# esp01-prog.net
KiCad netlist of a schematic drawn in EAGLE
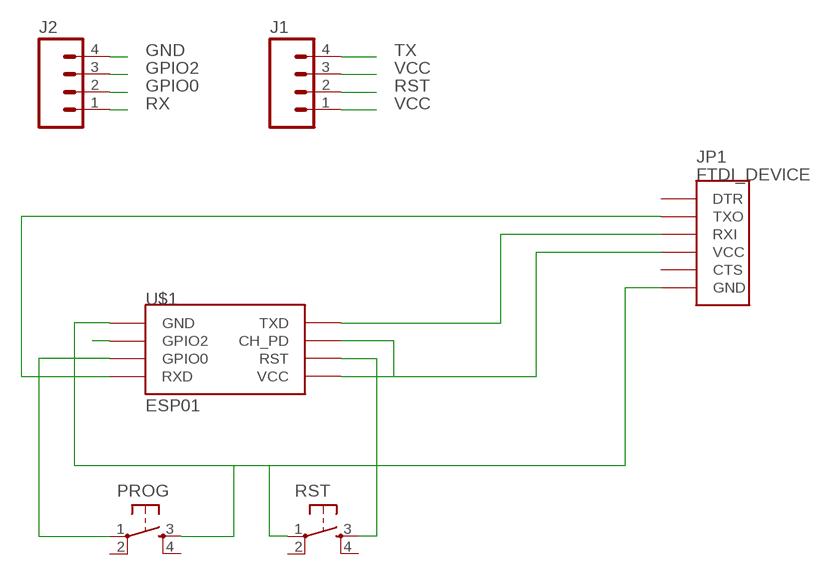
[diagram p0: schematic, sheet 1]

(export (version "E")
  (design (tool "Eeschema 10.0.6"))
  (components
    (comp (ref "J1")
      (value "M04PTH")
      (footprint "eagle-import:1X04")
      (libsource (lib "eagle-import") (part "M04PTH"))
    )
    (comp (ref "J2")
      (value "M04PTH")
      (footprint "eagle-import:1X04")
      (libsource (lib "eagle-import") (part "M04PTH"))
    )
    (comp (ref "JP1")
      (value "FTDI_DEVICE")
      (footprint "eagle-import:FTDI_DEVICE_SIDE")
      (libsource (lib "eagle-import") (part "FTDI_DEVICE"))
    )
    (comp (ref "PROG")
      (value "TACTILE-SWITCH-PTH")
      (footprint "eagle-import:TAC-SWITCH-PTH")
      (libsource (lib "eagle-import") (part "TACTILE-SWITCH-PTH"))
    )
    (comp (ref "RST")
      (value "TACTILE-SWITCH-PTH")
      (footprint "eagle-import:TAC-SWITCH-PTH")
      (libsource (lib "eagle-import") (part "TACTILE-SWITCH-PTH"))
    )
    (comp (ref "U$1")
      (value "ESP01")
      (footprint "eagle-import:ESP01")
      (libsource (lib "eagle-import") (part "ESP01"))
    )
  )
  (nets
    (net (code "1") (name "/GND") (class "Default")
      (node (ref "J2") (pin "4") (pinfunction "4_4") (pintype "passive"))
      (node (ref "JP1") (pin "P$6") (pinfunction "GND_P$6") (pintype "bidirectional"))
      (node (ref "PROG") (pin "3") (pinfunction "3_3") (pintype "passive"))
      (node (ref "RST") (pin "1") (pinfunction "1_1") (pintype "passive"))
      (node (ref "U$1") (pin "GND") (pinfunction "GND_GND") (pintype "bidirectional"))
    )
    (net (code "2") (name "/GPIO0") (class "Default")
      (node (ref "J2") (pin "2") (pinfunction "2_2") (pintype "passive"))
      (node (ref "PROG") (pin "1") (pinfunction "1_1") (pintype "passive"))
      (node (ref "U$1") (pin "GPIO0") (pinfunction "GPIO0_GPIO0") (pintype "bidirectional"))
    )
    (net (code "3") (name "/GPIO2") (class "Default")
      (node (ref "J2") (pin "3") (pinfunction "3_3") (pintype "passive"))
      (node (ref "U$1") (pin "GPIO2") (pinfunction "GPIO2_GPIO2") (pintype "bidirectional"))
    )
    (net (code "4") (name "/RST") (class "Default")
      (node (ref "J1") (pin "2") (pinfunction "2_2") (pintype "passive"))
      (node (ref "RST") (pin "3") (pinfunction "3_3") (pintype "passive"))
      (node (ref "U$1") (pin "RST") (pinfunction "RST_RST") (pintype "bidirectional"))
    )
    (net (code "5") (name "/RX") (class "Default")
      (node (ref "J2") (pin "1") (pinfunction "1_1") (pintype "passive"))
      (node (ref "JP1") (pin "P$2") (pinfunction "TXO_P$2") (pintype "bidirectional"))
      (node (ref "U$1") (pin "RX") (pinfunction "RXD_RX") (pintype "bidirectional"))
    )
    (net (code "6") (name "/TX") (class "Default")
      (node (ref "J1") (pin "4") (pinfunction "4_4") (pintype "passive"))
      (node (ref "JP1") (pin "P$3") (pinfunction "RXI_P$3") (pintype "bidirectional"))
      (node (ref "U$1") (pin "TX") (pinfunction "TXD_TX") (pintype "bidirectional"))
    )
    (net (code "7") (name "/VCC") (class "Default")
      (node (ref "J1") (pin "1") (pinfunction "1_1") (pintype "passive"))
      (node (ref "J1") (pin "3") (pinfunction "3_3") (pintype "passive"))
      (node (ref "JP1") (pin "P$4") (pinfunction "VCC_P$4") (pintype "bidirectional"))
      (node (ref "U$1") (pin "CH_PD") (pinfunction "CH_PD_CH_PD") (pintype "bidirectional"))
      (node (ref "U$1") (pin "VCC") (pinfunction "VCC_VCC") (pintype "bidirectional"))
    )
    (net (code "8") (name "unconnected-(JP1-CTS-PadP$5)") (class "Default")
      (node (ref "JP1") (pin "P$5") (pinfunction "CTS_P$5") (pintype "bidirectional"))
    )
    (net (code "9") (name "unconnected-(JP1-DTR-PadP$1)") (class "Default")
      (node (ref "JP1") (pin "P$1") (pinfunction "DTR_P$1") (pintype "bidirectional"))
    )
    (net (code "10") (name "unconnected-(PROG-Pad2)") (class "Default")
      (node (ref "PROG") (pin "2") (pinfunction "2_2") (pintype "passive"))
    )
    (net (code "11") (name "unconnected-(PROG-Pad4)") (class "Default")
      (node (ref "PROG") (pin "4") (pinfunction "4_4") (pintype "passive"))
    )
    (net (code "12") (name "unconnected-(RST-Pad2)") (class "Default")
      (node (ref "RST") (pin "2") (pinfunction "2_2") (pintype "passive"))
    )
    (net (code "13") (name "unconnected-(RST-Pad4)") (class "Default")
      (node (ref "RST") (pin "4") (pinfunction "4_4") (pintype "passive"))
    )
  )
)
